# Sensor.net
KiCad netlist of a schematic drawn in Altium Designer
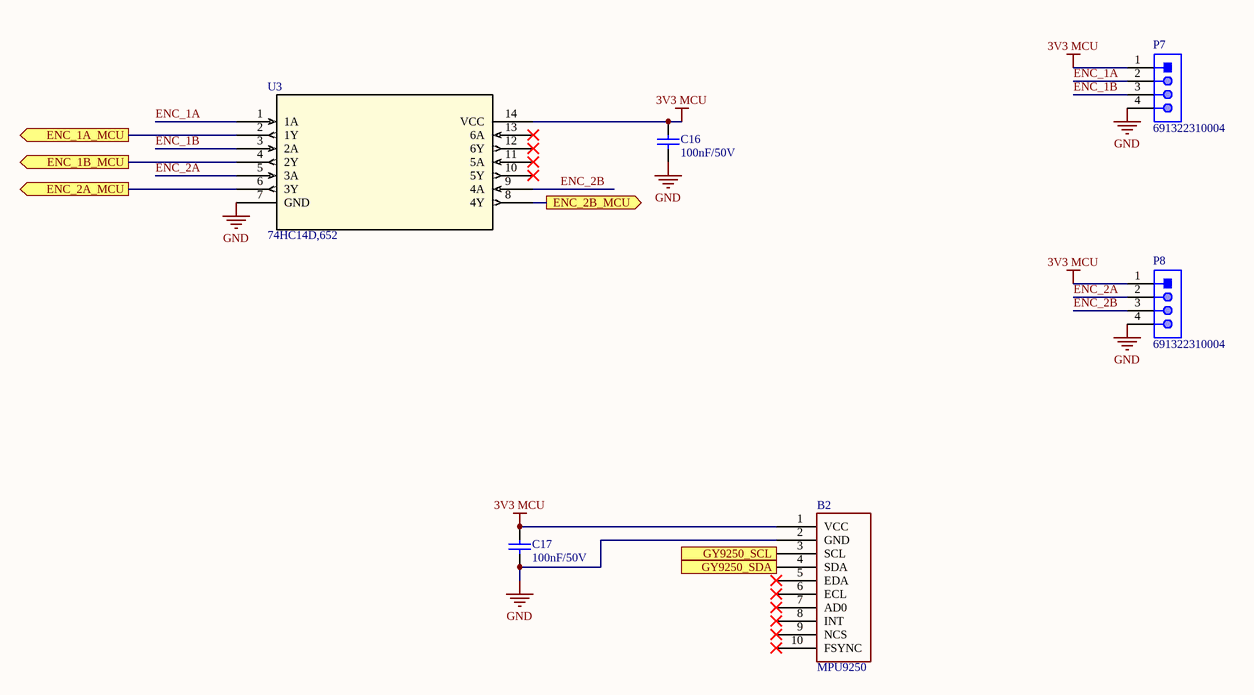
[diagram p0: Sensor.SchDoc]

(export (version "E")
  (design (tool "Eeschema 10.0.6"))
  (components
    (comp (ref "B2") (value "MPU9250") (footprint "MPU9250") (libsource (lib "Board") (part "MPU9250")))
    (comp (ref "C16")
      (value "100nF/50V")
      (footprint "CAP-SM-0805")
      (description "CAP CER 0.1UF 50V Y5V 0805")
      (fields
        (field (name "MANUFACTURER") "Samsung Electro-Mechanics")
        (field (name "MANUFACTURER PART NUMBER") "CL21F104ZBCNNNC")
      )
      (libsource (lib "Capacitor") (part "Cap-100nF-50V-0805"))
    )
    (comp (ref "C17")
      (value "100nF/50V")
      (footprint "CAP-SM-0805")
      (description "CAP CER 0.1UF 50V Y5V 0805")
      (fields
        (field (name "MANUFACTURER") "Samsung Electro-Mechanics")
        (field (name "MANUFACTURER PART NUMBER") "CL21F104ZBCNNNC")
      )
      (libsource (lib "Capacitor") (part "Cap-100nF-50V-0805"))
    )
    (comp (ref "P7")
      (value "691322310004")
      (footprint "Project_Xe_Can_Bang:691322310004")
      (description "WR-TBL Serie 322 Horizontal PCB Header, Pluggable, pitch 3.81mm, 4p")
      (fields (field (name "PUBLISHER") "Wurth Elektronik"))
      (libsource (lib "Project_Xe_Can_Bang") (part "691322310004"))
    )
    (comp (ref "P8")
      (value "691322310004")
      (footprint "Project_Xe_Can_Bang:691322310004")
      (description "WR-TBL Serie 322 Horizontal PCB Header, Pluggable, pitch 3.81mm, 4p")
      (fields (field (name "PUBLISHER") "Wurth Elektronik"))
      (libsource (lib "Project_Xe_Can_Bang") (part "691322310004"))
    )
    (comp (ref "U3")
      (value "74HC14D,652")
      (footprint "SOT108-1_NEX")
      (description "No Description Available")
      (fields (field (name "COPYRIGHT") "Copyright (C) 2016 Accelerated Designs. All rights reserved"))
      (libsource (lib "74HC14D_625_2020-06-19_15-46-23") (part "74HC14D,652"))
    )
  )
  (nets
    (net (code "1") (name "/ENC_1A") (class "Default")
      (node (ref "P7") (pin "2") (pinfunction "2_2") (pintype "passive"))
      (node (ref "U3") (pin "1") (pinfunction "1A_1") (pintype "input"))
    )
    (net (code "2") (name "/ENC_1A_MCU") (class "Default")
      (node (ref "U3") (pin "2") (pinfunction "1Y_2") (pintype "output"))
    )
    (net (code "3") (name "/ENC_1B") (class "Default")
      (node (ref "P7") (pin "3") (pinfunction "3_3") (pintype "passive"))
      (node (ref "U3") (pin "3") (pinfunction "2A_3") (pintype "input"))
    )
    (net (code "4") (name "/ENC_1B_MCU") (class "Default")
      (node (ref "U3") (pin "4") (pinfunction "2Y_4") (pintype "output"))
    )
    (net (code "5") (name "/ENC_2A") (class "Default")
      (node (ref "P8") (pin "2") (pinfunction "2_2") (pintype "passive"))
      (node (ref "U3") (pin "5") (pinfunction "3A_5") (pintype "input"))
    )
    (net (code "6") (name "/ENC_2A_MCU") (class "Default")
      (node (ref "U3") (pin "6") (pinfunction "3Y_6") (pintype "output"))
    )
    (net (code "7") (name "/ENC_2B") (class "Default")
      (node (ref "P8") (pin "3") (pinfunction "3_3") (pintype "passive"))
      (node (ref "U3") (pin "9") (pinfunction "4A_9") (pintype "input"))
    )
    (net (code "8") (name "/ENC_2B_MCU") (class "Default")
      (node (ref "U3") (pin "8") (pinfunction "4Y_8") (pintype "output"))
    )
    (net (code "9") (name "/GY9250_SCL") (class "Default")
      (node (ref "B2") (pin "3") (pinfunction "SCL_3") (pintype "passive"))
    )
    (net (code "10") (name "/GY9250_SDA") (class "Default")
      (node (ref "B2") (pin "4") (pinfunction "SDA_4") (pintype "passive"))
    )
    (net (code "11") (name "3V3 MCU") (class "Default")
      (node (ref "B2") (pin "1") (pinfunction "VCC_1") (pintype "passive"))
      (node (ref "C16") (pin "2") (pinfunction "2_2") (pintype "passive"))
      (node (ref "C17") (pin "2") (pinfunction "2_2") (pintype "passive"))
      (node (ref "P7") (pin "1") (pinfunction "1_1") (pintype "passive"))
      (node (ref "P8") (pin "1") (pinfunction "1_1") (pintype "passive"))
      (node (ref "U3") (pin "14") (pinfunction "VCC_14") (pintype "power_in"))
    )
    (net (code "12") (name "GND") (class "Default")
      (node (ref "B2") (pin "2") (pinfunction "GND_2") (pintype "passive"))
      (node (ref "C16") (pin "1") (pinfunction "1_1") (pintype "passive"))
      (node (ref "C17") (pin "1") (pinfunction "1_1") (pintype "passive"))
      (node (ref "P7") (pin "4") (pinfunction "4_4") (pintype "passive"))
      (node (ref "P8") (pin "4") (pinfunction "4_4") (pintype "passive"))
      (node (ref "U3") (pin "7") (pinfunction "GND_7") (pintype "power_in"))
    )
    (net (code "13") (name "unconnected-(B2-AD0-Pad7)") (class "Default")
      (node (ref "B2") (pin "7") (pinfunction "AD0_7") (pintype "passive+no_connect"))
    )
    (net (code "14") (name "unconnected-(B2-ECL-Pad6)") (class "Default")
      (node (ref "B2") (pin "6") (pinfunction "ECL_6") (pintype "passive+no_connect"))
    )
    (net (code "15") (name "unconnected-(B2-EDA-Pad5)") (class "Default")
      (node (ref "B2") (pin "5") (pinfunction "EDA_5") (pintype "passive+no_connect"))
    )
    (net (code "16") (name "unconnected-(B2-FSYNC-Pad10)") (class "Default")
      (node (ref "B2") (pin "10") (pinfunction "FSYNC_10") (pintype "passive+no_connect"))
    )
    (net (code "17") (name "unconnected-(B2-INT-Pad8)") (class "Default")
      (node (ref "B2") (pin "8") (pinfunction "INT_8") (pintype "passive+no_connect"))
    )
    (net (code "18") (name "unconnected-(B2-NCS-Pad9)") (class "Default")
      (node (ref "B2") (pin "9") (pinfunction "NCS_9") (pintype "passive+no_connect"))
    )
    (net (code "19") (name "unconnected-(U3-5A-Pad11)") (class "Default")
      (node (ref "U3") (pin "11") (pinfunction "5A_11") (pintype "input+no_connect"))
    )
    (net (code "20") (name "unconnected-(U3-5Y-Pad10)") (class "Default")
      (node (ref "U3") (pin "10") (pinfunction "5Y_10") (pintype "output+no_connect"))
    )
    (net (code "21") (name "unconnected-(U3-6A-Pad13)") (class "Default")
      (node (ref "U3") (pin "13") (pinfunction "6A_13") (pintype "input+no_connect"))
    )
    (net (code "22") (name "unconnected-(U3-6Y-Pad12)") (class "Default")
      (node (ref "U3") (pin "12") (pinfunction "6Y_12") (pintype "output+no_connect"))
    )
  )
)
